# TSAL_REV2_2.net
KiCad netlist of a schematic drawn in Altium Designer
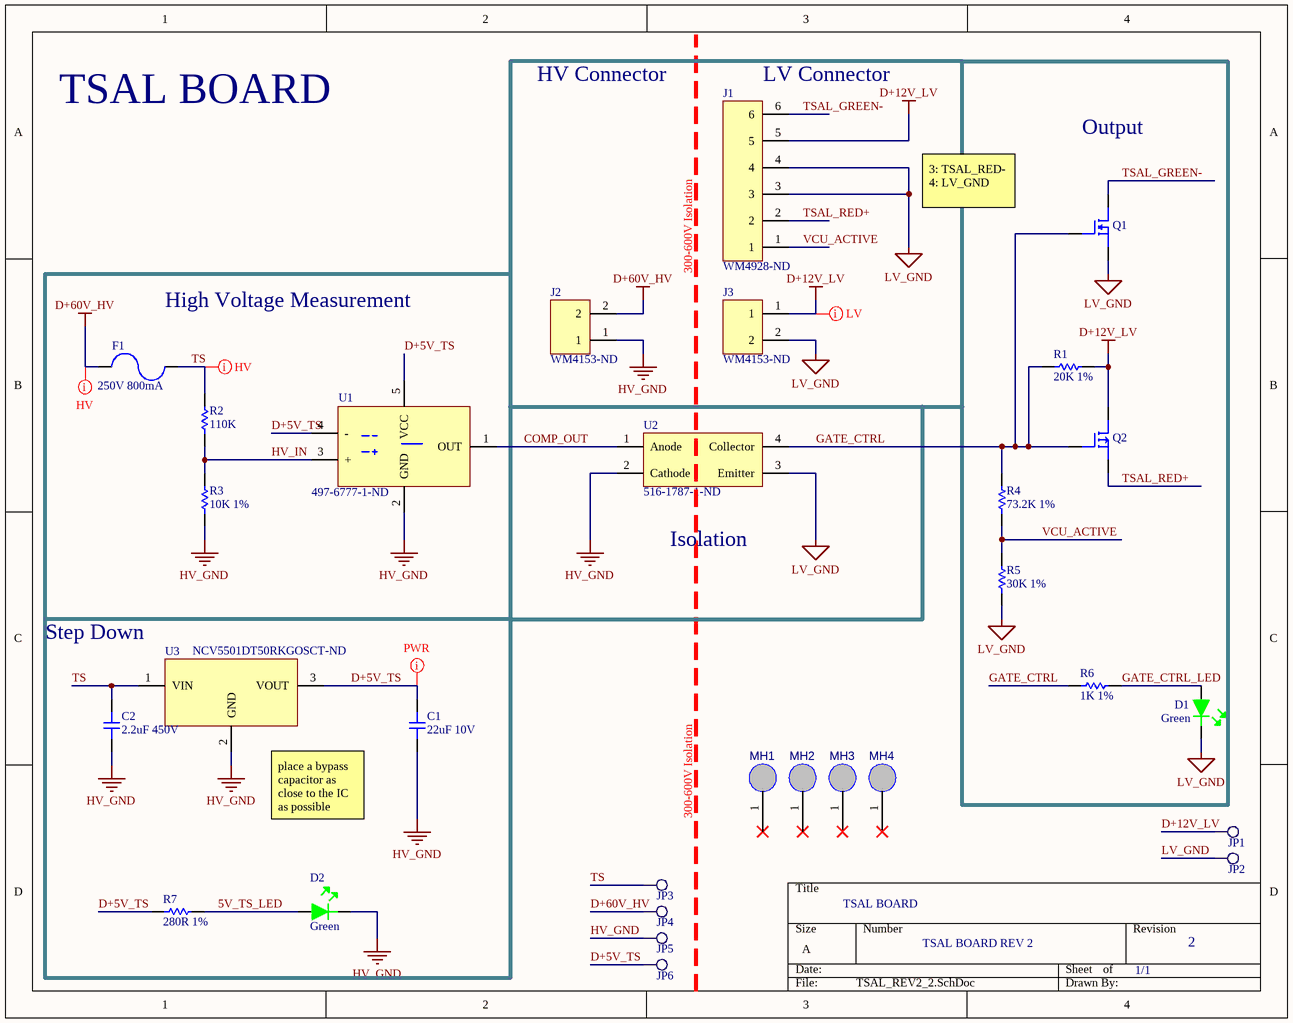
[diagram p0: TSAL_REV2_2.SchDoc]

(export (version "E")
  (design (tool "Eeschema 10.0.6"))
  (components
    (comp (ref "C1")
      (value "22uF 10V")
      (footprint "CAP-0805")
      (description "CAP CER 22UF 10V X5R 0805")
      (fields
        (field (name "MANUFACTURER") "KEMET")
        (field (name "MANUFACTURER PART NUMBER") "C0805C226M8PACTU")
      )
      (libsource (lib "Capacitors") (part "0805-22uF-10V"))
    )
    (comp (ref "C2")
      (value "2.2uF 450V")
      (footprint "CAP-2220")
      (description "CAP CER 2.2UF 450V X6S 2220")
      (fields
        (field (name "MANUFACTURER") "TDK")
        (field (name "MANUFACTURER PART NUMBER") "C5750X6S2W225K250KA")
      )
      (libsource (lib "Capacitors") (part "2220-2.2uF-450V"))
    )
    (comp (ref "D1")
      (value "Green")
      (footprint "LED-0603")
      (description "LED GREEN CLEAR 0603 SMD")
      (fields
        (field (name "MANUFACTURER") "Wurth Electronics")
        (field (name "MANUFACTURER PART NUMBER") "150060VS75000")
      )
      (libsource (lib "LEDs") (part "LED-Green"))
    )
    (comp (ref "D2")
      (value "Green")
      (footprint "LED-0603")
      (description "LED GREEN CLEAR 0603 SMD")
      (fields
        (field (name "MANUFACTURER") "Wurth Electronics")
        (field (name "MANUFACTURER PART NUMBER") "150060VS75000")
      )
      (libsource (lib "LEDs") (part "LED-Green"))
    )
    (comp (ref "F1")
      (value "250V 800mA")
      (footprint "Fuse-10x3")
      (description "FUSE SMT 3912 FAST 250V 800MA")
      (fields (field (name "MANUFACTURER") "Bel") (field (name "MANUFACTURER PART NUMBER") "0678D0800-02"))
      (libsource (lib "Misc") (part "Fuse 250V-0.8A"))
    )
    (comp (ref "J1")
      (value "WM4928-ND")
      (footprint "6PIN")
      (description "CONN HEADER R/A 6POS 2.54MM")
      (fields (field (name "MANUFACTURER") "Molex") (field (name "MANUFACTURER PART NUMBER") "70553-0040"))
      (libsource (lib "Connectors") (part "6PIN"))
    )
    (comp (ref "J2")
      (value "WM4153-ND")
      (footprint "2PIN")
      (description "CONN HEADER R/A 2POS 2.54MM")
      (fields (field (name "MANUFACTURER") "Molex") (field (name "MANUFACTURER PART NUMBER") "0705530106"))
      (libsource (lib "Connectors") (part "2PIN"))
    )
    (comp (ref "J3")
      (value "WM4153-ND")
      (footprint "2PIN")
      (description "CONN HEADER R/A 2POS 2.54MM")
      (fields (field (name "MANUFACTURER") "Molex") (field (name "MANUFACTURER PART NUMBER") "0705530106"))
      (libsource (lib "") (part "2PIN_1"))
    )
    (comp (ref "JP1")
      (value "Testpoint2")
      (footprint "TP2")
      (description "Single layer pad TP")
      (libsource (lib "Misc") (part "Testpoint2"))
    )
    (comp (ref "JP2")
      (value "Testpoint2")
      (footprint "TP2")
      (description "Single layer pad TP")
      (libsource (lib "Misc") (part "Testpoint2"))
    )
    (comp (ref "JP3")
      (value "Testpoint2")
      (footprint "TP2")
      (description "Single layer pad TP")
      (libsource (lib "Misc") (part "Testpoint2"))
    )
    (comp (ref "JP4")
      (value "Testpoint2")
      (footprint "TP2")
      (description "Single layer pad TP")
      (libsource (lib "Misc") (part "Testpoint2"))
    )
    (comp (ref "JP5")
      (value "Testpoint2")
      (footprint "TP2")
      (description "Single layer pad TP")
      (libsource (lib "Misc") (part "Testpoint2"))
    )
    (comp (ref "JP6")
      (value "Testpoint2")
      (footprint "TP2")
      (description "Single layer pad TP")
      (libsource (lib "Misc") (part "Testpoint2"))
    )
    (comp (ref "MH1")
      (value "MountingHole")
      (footprint "MH4.2MM")
      (description "Mounting hole, 4.2mm")
      (libsource (lib "New_Parts") (part "MH4.2mm"))
    )
    (comp (ref "MH2")
      (value "MountingHole")
      (footprint "MH4.2MM")
      (description "Mounting hole, 4.2mm")
      (libsource (lib "New_Parts") (part "MH4.2mm"))
    )
    (comp (ref "MH3")
      (value "MountingHole")
      (footprint "MH4.2MM")
      (description "Mounting hole, 4.2mm")
      (libsource (lib "New_Parts") (part "MH4.2mm"))
    )
    (comp (ref "MH4")
      (value "MountingHole")
      (footprint "MH4.2MM")
      (description "Mounting hole, 4.2mm")
      (libsource (lib "New_Parts") (part "MH4.2mm"))
    )
    (comp (ref "Q1")
      (value "IPD50N06S4L12ATMA2CT-ND")
      (footprint "DPAK-TO252")
      (description "MOSFET N-CH 60V 50A TO252-3")
      (fields
        (field (name "MANUFACTURER") "Infineon")
        (field (name "MANUFACTURER PART NUMBER") "IPD50N06S4L12ATMA2")
      )
      (libsource (lib "Transistors") (part "N-FET-60V-50A"))
    )
    (comp (ref "Q2")
      (value "NTD2955T4GOSCT-ND")
      (footprint "DPAK-TO252")
      (description "MOSFET P-CH 60V 12A DPAK")
      (fields
        (field (name "MANUFACTURER") "ON Semiconductor")
        (field (name "MANUFACTURER PART NUMBER") "NTD2955T4G")
      )
      (libsource (lib "Transistors") (part "P-FET-60V-12A"))
    )
    (comp (ref "R1")
      (value "20K 1%")
      (footprint "RES-0603")
      (description "RES SMD 20K OHM 1% 1/10W 0603")
      (fields
        (field (name "MANUFACTURER") "Yageo")
        (field (name "MANUFACTURER PART NUMBER") "RC0603FR-0720KL")
      )
      (libsource (lib "Resistors") (part "0603-20KR"))
    )
    (comp (ref "R2")
      (value "110K")
      (footprint "RES-0805")
      (description "RES SMD 110K OHM 1% 1/8W 0805")
      (fields
        (field (name "MANUFACTURER") "Yageo")
        (field (name "MANUFACTURER PART NUMBER") "RC0805FR-07110KL")
      )
      (libsource (lib "Resistors") (part "0805-110KR"))
    )
    (comp (ref "R3")
      (value "10K 1%")
      (footprint "RES-0805")
      (description "RES SMD 10K OHM 1% 1/8W 0805")
      (fields
        (field (name "MANUFACTURER") "Yageo")
        (field (name "MANUFACTURER PART NUMBER") "RC0805FR-0710KL")
      )
      (libsource (lib "Resistors") (part "0805-10KR"))
    )
    (comp (ref "R4")
      (value "73.2K 1%")
      (footprint "RES-0603")
      (description "RES SMD 73.2K OHM 1% 1/10W 0603")
      (fields
        (field (name "MANUFACTURER") "Yageo")
        (field (name "MANUFACTURER PART NUMBER") "RC0603FR-0773K2L")
      )
      (libsource (lib "Resistors") (part "0603-73.2KR"))
    )
    (comp (ref "R5")
      (value "30K 1%")
      (footprint "RES-0603")
      (description "RES SMD 30K OHM 1% 1/10W 0603")
      (fields
        (field (name "MANUFACTURER") "Yageo")
        (field (name "MANUFACTURER PART NUMBER") "RC0603FR-0730KL")
      )
      (libsource (lib "Resistors") (part "0603-30KR"))
    )
    (comp (ref "R6")
      (value "1K 1%")
      (footprint "RES-0603")
      (description "RES SMD 1K OHM 1% 1/10W 0603")
      (fields
        (field (name "MANUFACTURER") "Vishay Dale")
        (field (name "MANUFACTURER PART NUMBER") "CRCW06031K00FKEA")
      )
      (libsource (lib "Resistors") (part "0603-1KR"))
    )
    (comp (ref "R7")
      (value "280R 1%")
      (footprint "RES-0603")
      (description "RES SMD 280 OHM 1% 1/10W 0603")
      (fields
        (field (name "MANUFACTURER") "Yageo")
        (field (name "MANUFACTURER PART NUMBER") "RC0603FR-07280RL")
      )
      (libsource (lib "Resistors") (part "0603-280R"))
    )
    (comp (ref "U1")
      (value "497-6777-1-ND")
      (footprint "SOT-23-5")
      (description "IC COMPARATOR R-R MCRPWR SOT23-5")
      (fields
        (field (name "MANUFACTURER") "STMicroelectronics")
        (field (name "MANUFACTURER PART NUMBER") "TS861ILT")
      )
      (libsource (lib "Logic") (part "Compare-TS861ILT"))
    )
    (comp (ref "U2")
      (value "516-1787-1-ND")
      (footprint "4-SSOP")
      (description "OPTOISO 3.75KV TRANS 4MINIFLAT")
      (fields
        (field (name "MANUFACTURER") "Broadcom Avago")
        (field (name "MANUFACTURER PART NUMBER") "HCPL-181-00BE")
      )
      (libsource (lib "ICs") (part "OPTO-ISO-3.75kV"))
    )
    (comp (ref "U3")
      (value "NCV5501DT50RKGOSCT-ND")
      (footprint "DPAK-TO252")
      (description "IC REG LINEAR 5V 500MA DPAK")
      (fields
        (field (name "MANUFACTURER") "ON Semiconductor")
        (field (name "MANUFACTURER PART NUMBER") "NCV5501DT50RKG")
      )
      (libsource (lib "Power") (part "LDO-5V-500mA"))
    )
  )
  (nets
    (net (code "1") (name "/5V_TS_LED") (class "Default")
      (node (ref "D2") (pin "1") (pinfunction "1_1") (pintype "passive"))
      (node (ref "R7") (pin "2") (pinfunction "2_2") (pintype "passive"))
    )
    (net (code "2") (name "/COMP_OUT") (class "Default")
      (node (ref "U1") (pin "1") (pinfunction "OUT_1") (pintype "passive"))
      (node (ref "U2") (pin "1") (pinfunction "Anode_1") (pintype "passive"))
    )
    (net (code "3") (name "/D+5V_TS") (class "Default")
      (node (ref "C1") (pin "2") (pinfunction "2_2") (pintype "passive"))
      (node (ref "JP6") (pin "1") (pinfunction "1_1") (pintype "passive"))
      (node (ref "R7") (pin "1") (pinfunction "1_1") (pintype "passive"))
      (node (ref "U1") (pin "4") (pinfunction "-_4") (pintype "passive"))
      (node (ref "U1") (pin "5") (pinfunction "VCC_5") (pintype "passive"))
      (node (ref "U3") (pin "3") (pinfunction "VOUT_3") (pintype "passive"))
    )
    (net (code "4") (name "/GATE_CTRL") (class "Default")
      (node (ref "Q1") (pin "1") (pinfunction "1_1") (pintype "passive"))
      (node (ref "Q2") (pin "1") (pinfunction "1_1") (pintype "passive"))
      (node (ref "R1") (pin "1") (pinfunction "1_1") (pintype "passive"))
      (node (ref "R4") (pin "2") (pinfunction "2_2") (pintype "passive"))
      (node (ref "R6") (pin "1") (pinfunction "1_1") (pintype "passive"))
      (node (ref "U2") (pin "4") (pinfunction "Collector_4") (pintype "passive"))
    )
    (net (code "5") (name "/GATE_CTRL_LED") (class "Default")
      (node (ref "D1") (pin "1") (pinfunction "1_1") (pintype "passive"))
      (node (ref "R6") (pin "2") (pinfunction "2_2") (pintype "passive"))
    )
    (net (code "6") (name "/HV_IN") (class "Default")
      (node (ref "R2") (pin "1") (pinfunction "1_1") (pintype "passive"))
      (node (ref "R3") (pin "2") (pinfunction "2_2") (pintype "passive"))
      (node (ref "U1") (pin "3") (pinfunction "+_3") (pintype "passive"))
    )
    (net (code "7") (name "/TS") (class "Default")
      (node (ref "C2") (pin "1") (pinfunction "1_1") (pintype "passive"))
      (node (ref "F1") (pin "2") (pinfunction "2_2") (pintype "passive"))
      (node (ref "JP3") (pin "1") (pinfunction "1_1") (pintype "passive"))
      (node (ref "R2") (pin "2") (pinfunction "2_2") (pintype "passive"))
      (node (ref "U3") (pin "1") (pinfunction "VIN_1") (pintype "passive"))
    )
    (net (code "8") (name "/TSAL_GREEN-") (class "Default")
      (node (ref "J1") (pin "6") (pinfunction "6_6") (pintype "passive"))
      (node (ref "Q1") (pin "2") (pinfunction "2_2") (pintype "passive"))
    )
    (net (code "9") (name "/TSAL_RED+") (class "Default")
      (node (ref "J1") (pin "2") (pinfunction "2_2") (pintype "passive"))
      (node (ref "Q2") (pin "3") (pinfunction "3_3") (pintype "passive"))
    )
    (net (code "10") (name "/VCU_ACTIVE") (class "Default")
      (node (ref "J1") (pin "1") (pinfunction "1_1") (pintype "passive"))
      (node (ref "R4") (pin "1") (pinfunction "1_1") (pintype "passive"))
      (node (ref "R5") (pin "2") (pinfunction "2_2") (pintype "passive"))
    )
    (net (code "11") (name "D+12V_LV") (class "Default")
      (node (ref "J1") (pin "5") (pinfunction "5_5") (pintype "passive"))
      (node (ref "J3") (pin "1") (pinfunction "1_1") (pintype "passive"))
      (node (ref "JP1") (pin "1") (pinfunction "1_1") (pintype "passive"))
      (node (ref "Q2") (pin "2") (pinfunction "2_2") (pintype "passive"))
      (node (ref "R1") (pin "2") (pinfunction "2_2") (pintype "passive"))
    )
    (net (code "12") (name "D+60V_HV") (class "Default")
      (node (ref "F1") (pin "1") (pinfunction "1_1") (pintype "passive"))
      (node (ref "J2") (pin "2") (pinfunction "2_2") (pintype "passive"))
      (node (ref "JP4") (pin "1") (pinfunction "1_1") (pintype "passive"))
    )
    (net (code "13") (name "HV_GND") (class "Default")
      (node (ref "C1") (pin "1") (pinfunction "1_1") (pintype "passive"))
      (node (ref "C2") (pin "2") (pinfunction "2_2") (pintype "passive"))
      (node (ref "D2") (pin "2") (pinfunction "2_2") (pintype "passive"))
      (node (ref "J2") (pin "1") (pinfunction "1_1") (pintype "passive"))
      (node (ref "JP5") (pin "1") (pinfunction "1_1") (pintype "passive"))
      (node (ref "R3") (pin "1") (pinfunction "1_1") (pintype "passive"))
      (node (ref "U1") (pin "2") (pinfunction "GND_2") (pintype "passive"))
      (node (ref "U2") (pin "2") (pinfunction "Cathode_2") (pintype "passive"))
      (node (ref "U3") (pin "2") (pinfunction "GND_2") (pintype "passive"))
    )
    (net (code "14") (name "LV_GND") (class "Default")
      (node (ref "D1") (pin "2") (pinfunction "2_2") (pintype "passive"))
      (node (ref "J1") (pin "3") (pinfunction "3_3") (pintype "passive"))
      (node (ref "J1") (pin "4") (pinfunction "4_4") (pintype "passive"))
      (node (ref "J3") (pin "2") (pinfunction "2_2") (pintype "passive"))
      (node (ref "JP2") (pin "1") (pinfunction "1_1") (pintype "passive"))
      (node (ref "Q1") (pin "3") (pinfunction "3_3") (pintype "passive"))
      (node (ref "R5") (pin "1") (pinfunction "1_1") (pintype "passive"))
      (node (ref "U2") (pin "3") (pinfunction "Emitter_3") (pintype "passive"))
    )
    (net (code "15") (name "unconnected-(MH1-Pad1)") (class "Default")
      (node (ref "MH1") (pin "1") (pintype "passive+no_connect"))
    )
    (net (code "16") (name "unconnected-(MH2-Pad1)") (class "Default")
      (node (ref "MH2") (pin "1") (pintype "passive+no_connect"))
    )
    (net (code "17") (name "unconnected-(MH3-Pad1)") (class "Default")
      (node (ref "MH3") (pin "1") (pintype "passive+no_connect"))
    )
    (net (code "18") (name "unconnected-(MH4-Pad1)") (class "Default")
      (node (ref "MH4") (pin "1") (pintype "passive+no_connect"))
    )
  )
)
